# nixie-clock.net
KiCad netlist of a schematic drawn in EAGLE
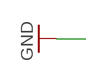
[diagram p0: schematic, sheet 1, part 1 of 2]
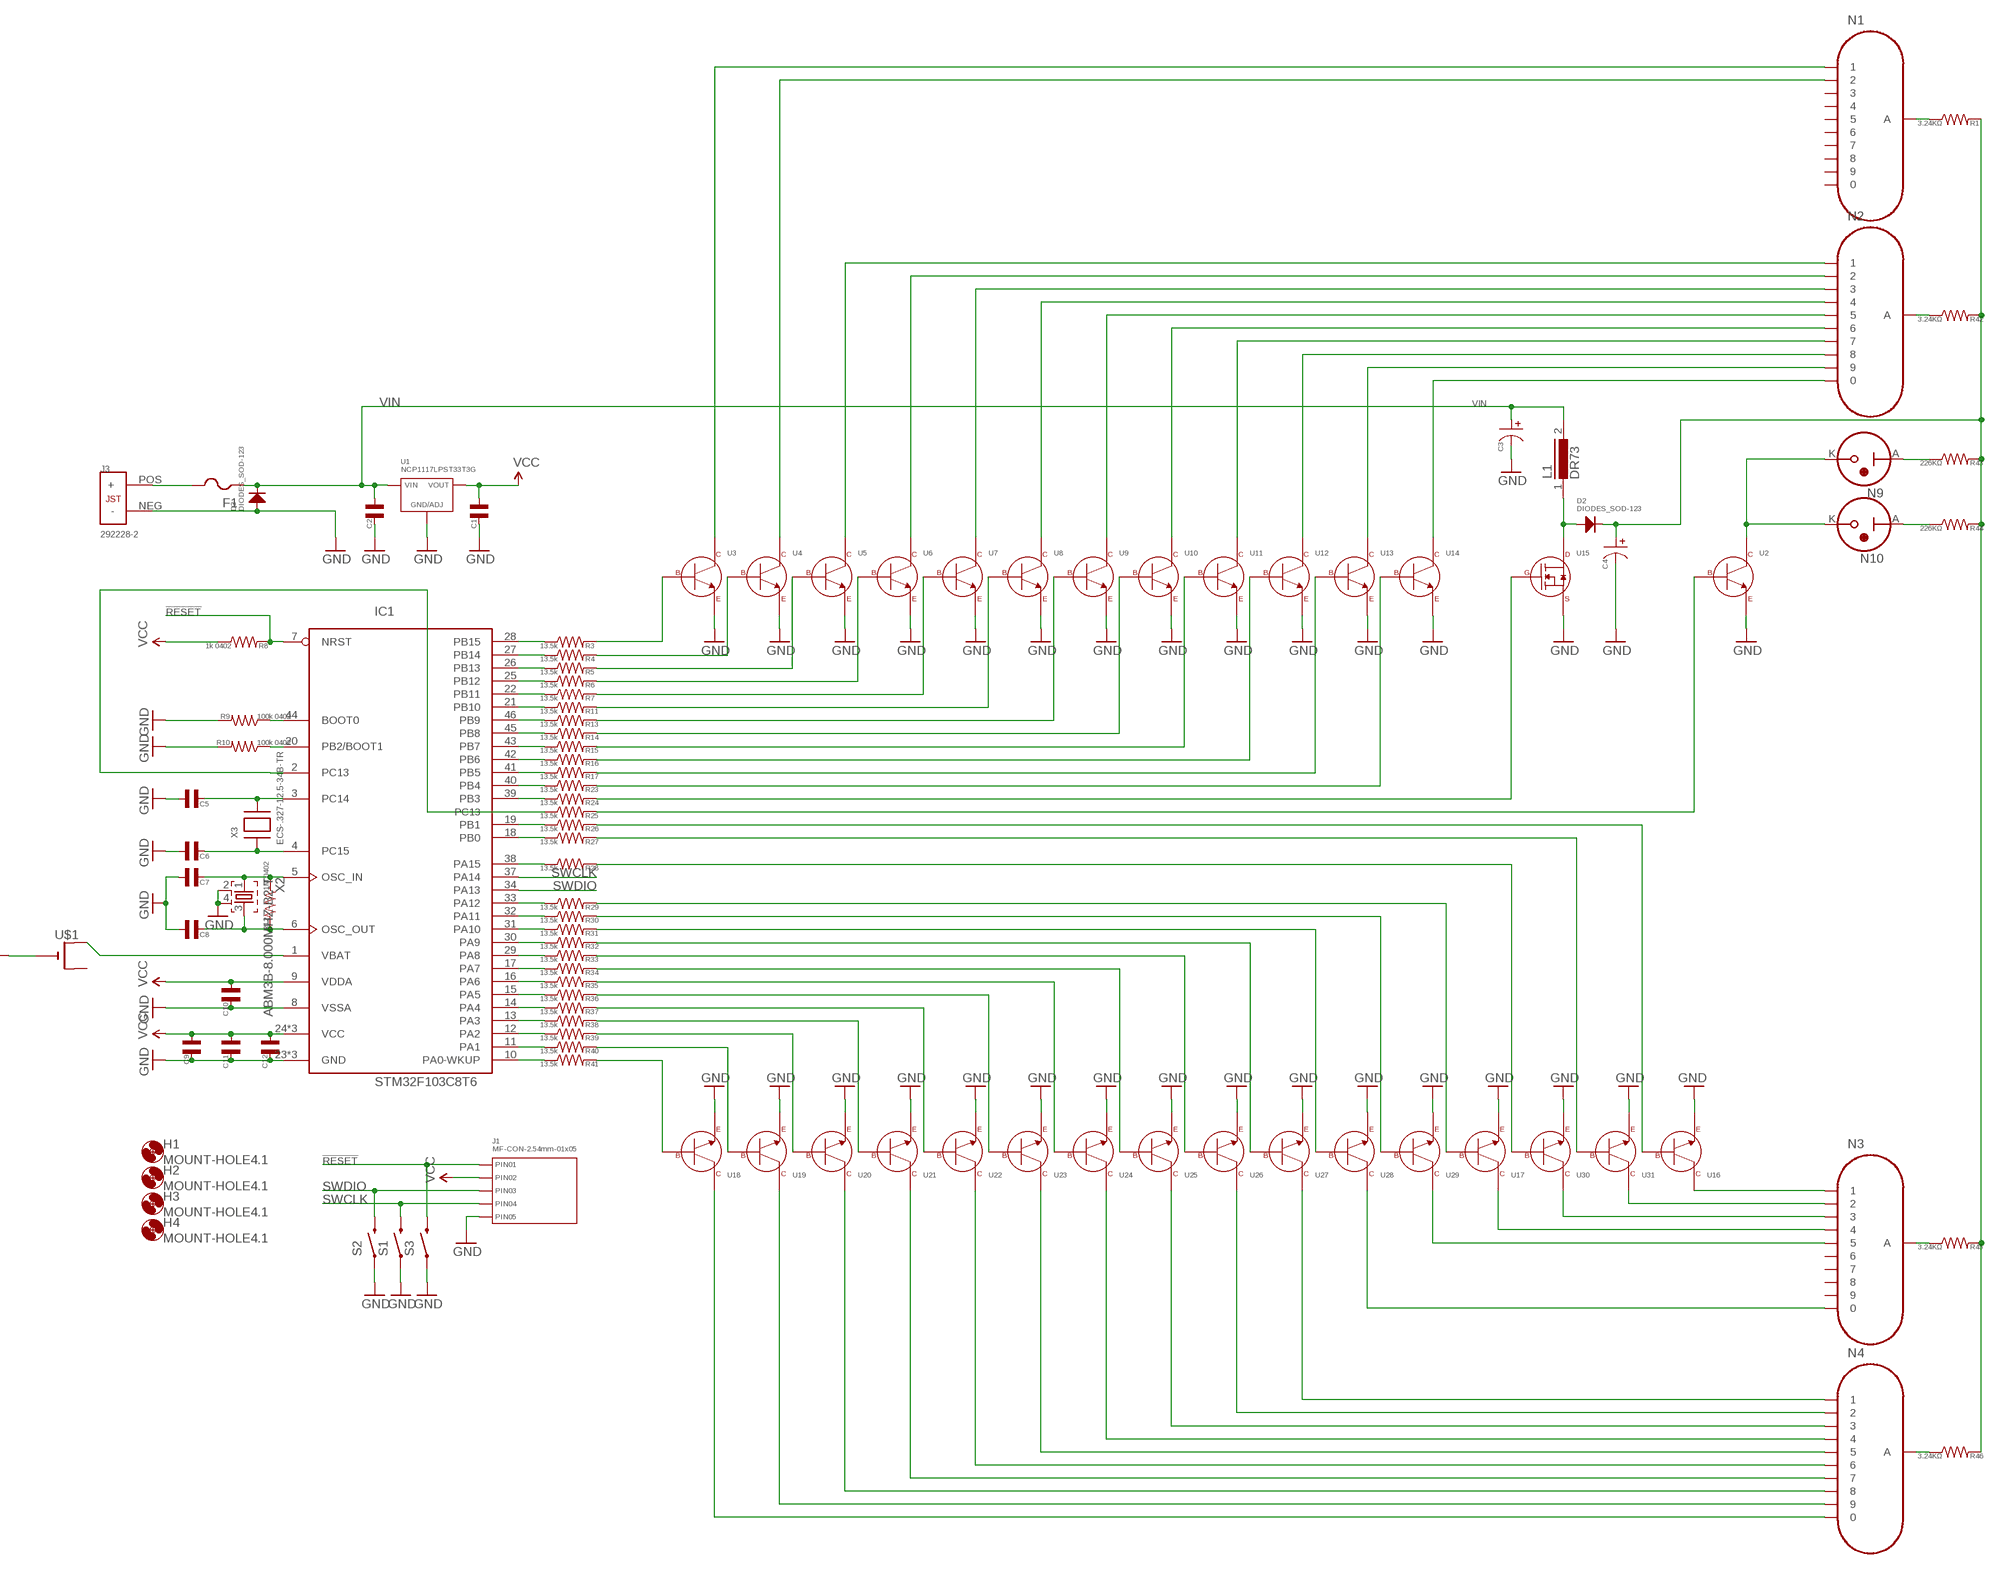
[diagram p1: schematic, sheet 1, part 2 of 2]

(export (version "E")
  (design (tool "Eeschema 10.0.6"))
  (components
    (comp (ref "C1")
      (value "CAPACITOR_NP_1206")
      (footprint "eagle-import:C1206")
      (libsource (lib "eagle-import") (part "CAPACITOR_NP_1206"))
    )
    (comp (ref "C2")
      (value "CAPACITOR_NP_1206")
      (footprint "eagle-import:C1206")
      (libsource (lib "eagle-import") (part "CAPACITOR_NP_1206"))
    )
    (comp (ref "C3")
      (value "CAPACITOR_P_6.3MM")
      (footprint "eagle-import:CP6.3MM")
      (libsource (lib "eagle-import") (part "CAPACITOR_P_6.3MM"))
    )
    (comp (ref "C4")
      (value "CAPACITOR_P_6.3MM")
      (footprint "eagle-import:CP6.3MM")
      (libsource (lib "eagle-import") (part "CAPACITOR_P_6.3MM"))
    )
    (comp (ref "C5")
      (value "CAPACITOR_NP_0402")
      (footprint "eagle-import:C0402")
      (libsource (lib "eagle-import") (part "CAPACITOR_NP_0402"))
    )
    (comp (ref "C6")
      (value "CAPACITOR_NP_0402")
      (footprint "eagle-import:C0402")
      (libsource (lib "eagle-import") (part "CAPACITOR_NP_0402"))
    )
    (comp (ref "C7")
      (value "CAPACITOR_NP_0402")
      (footprint "eagle-import:C0402")
      (libsource (lib "eagle-import") (part "CAPACITOR_NP_0402"))
    )
    (comp (ref "C8")
      (value "CAPACITOR_NP_0402")
      (footprint "eagle-import:C0402")
      (libsource (lib "eagle-import") (part "CAPACITOR_NP_0402"))
    )
    (comp (ref "C9")
      (value "CAPACITOR_NP_0402")
      (footprint "eagle-import:C0402")
      (libsource (lib "eagle-import") (part "CAPACITOR_NP_0402"))
    )
    (comp (ref "C10")
      (value "CAPACITOR_NP_0402")
      (footprint "eagle-import:C0402")
      (libsource (lib "eagle-import") (part "CAPACITOR_NP_0402"))
    )
    (comp (ref "C11")
      (value "CAPACITOR_NP_0402")
      (footprint "eagle-import:C0402")
      (libsource (lib "eagle-import") (part "CAPACITOR_NP_0402"))
    )
    (comp (ref "C12")
      (value "CAPACITOR_NP_0402")
      (footprint "eagle-import:C0402")
      (libsource (lib "eagle-import") (part "CAPACITOR_NP_0402"))
    )
    (comp (ref "D2")
      (value "DIODES_SOD-123")
      (footprint "eagle-import:SOD-123")
      (fields (field (name "HOUSEPART") "NO"))
      (libsource (lib "eagle-import") (part "DIODES_SOD-123"))
    )
    (comp (ref "D3")
      (value "DIODES_SOD-123")
      (footprint "eagle-import:SOD-123")
      (fields (field (name "HOUSEPART") "NO"))
      (libsource (lib "eagle-import") (part "DIODES_SOD-123"))
    )
    (comp (ref "F1")
      (value "PTCFUSE-1812")
      (footprint "eagle-import:1812")
      (libsource (lib "eagle-import") (part "PTCFUSE-1812"))
    )
    (comp (ref "H1")
      (value "MOUNT-HOLE4.1")
      (footprint "eagle-import:4,1")
      (libsource (lib "eagle-import") (part "MOUNT-HOLE4.1"))
    )
    (comp (ref "H2")
      (value "MOUNT-HOLE4.1")
      (footprint "eagle-import:4,1")
      (libsource (lib "eagle-import") (part "MOUNT-HOLE4.1"))
    )
    (comp (ref "H3")
      (value "MOUNT-HOLE4.1")
      (footprint "eagle-import:4,1")
      (libsource (lib "eagle-import") (part "MOUNT-HOLE4.1"))
    )
    (comp (ref "H4")
      (value "MOUNT-HOLE4.1")
      (footprint "eagle-import:4,1")
      (libsource (lib "eagle-import") (part "MOUNT-HOLE4.1"))
    )
    (comp (ref "IC1")
      (value "STM32F103C8T6")
      (footprint "eagle-import:LQFP48")
      (libsource (lib "eagle-import") (part "STM32F103CT8"))
    )
    (comp (ref "J1")
      (value "MF-CON-2.54mm-01x05")
      (footprint "eagle-import:PTH_2.54MM_01X05")
      (fields (field (name "HOUSEPART") "YES"))
      (libsource (lib "eagle-import") (part "CON_01X05_PTH_2.54MM"))
    )
    (comp (ref "J3")
      (value "292228-2")
      (footprint "eagle-import:292228-2")
      (libsource (lib "eagle-import") (part "MINICT"))
    )
    (comp (ref "L1")
      (value "DR73")
      (footprint "eagle-import:DR73")
      (libsource (lib "eagle-import") (part "DR73"))
    )
    (comp (ref "N1")
      (value "Hour1")
      (footprint "eagle-import:IN-4")
      (libsource (lib "eagle-import") (part "IN-4"))
    )
    (comp (ref "N2")
      (value "Hour2")
      (footprint "eagle-import:IN-4")
      (libsource (lib "eagle-import") (part "IN-4"))
    )
    (comp (ref "N3")
      (value "Minutes1")
      (footprint "eagle-import:IN-4")
      (libsource (lib "eagle-import") (part "IN-4"))
    )
    (comp (ref "N4")
      (value "Minutes2")
      (footprint "eagle-import:IN-4")
      (libsource (lib "eagle-import") (part "IN-4"))
    )
    (comp (ref "N9")
      (value "RainyBulb")
      (footprint "eagle-import:INS-1")
      (libsource (lib "eagle-import") (part "INS-1"))
    )
    (comp (ref "N10")
      (value "SnowyBulb")
      (footprint "eagle-import:INS-1")
      (libsource (lib "eagle-import") (part "INS-1"))
    )
    (comp (ref "R1")
      (value "3.24KΩ")
      (footprint "eagle-import:R0402")
      (libsource (lib "eagle-import") (part "RESISTOR_0402"))
    )
    (comp (ref "R3")
      (value "13.5k")
      (footprint "eagle-import:R0402")
      (libsource (lib "eagle-import") (part "RESISTOR_0402"))
    )
    (comp (ref "R4")
      (value "13.5k")
      (footprint "eagle-import:R0402")
      (libsource (lib "eagle-import") (part "RESISTOR_0402"))
    )
    (comp (ref "R5")
      (value "13.5k")
      (footprint "eagle-import:R0402")
      (libsource (lib "eagle-import") (part "RESISTOR_0402"))
    )
    (comp (ref "R6")
      (value "13.5k")
      (footprint "eagle-import:R0402")
      (libsource (lib "eagle-import") (part "RESISTOR_0402"))
    )
    (comp (ref "R7")
      (value "13.5k")
      (footprint "eagle-import:R0402")
      (libsource (lib "eagle-import") (part "RESISTOR_0402"))
    )
    (comp (ref "R8")
      (value "1k 0402")
      (footprint "eagle-import:R0402")
      (libsource (lib "eagle-import") (part "RESISTOR_0402"))
    )
    (comp (ref "R9")
      (value "100k 0402")
      (footprint "eagle-import:R0402")
      (libsource (lib "eagle-import") (part "RESISTOR_0402"))
    )
    (comp (ref "R10")
      (value "100k 0402")
      (footprint "eagle-import:R0402")
      (libsource (lib "eagle-import") (part "RESISTOR_0402"))
    )
    (comp (ref "R11")
      (value "13.5k")
      (footprint "eagle-import:R0402")
      (libsource (lib "eagle-import") (part "RESISTOR_0402"))
    )
    (comp (ref "R12")
      (value "1M 0402")
      (footprint "eagle-import:R0402")
      (libsource (lib "eagle-import") (part "RESISTOR_0402"))
    )
    (comp (ref "R13")
      (value "13.5k")
      (footprint "eagle-import:R0402")
      (libsource (lib "eagle-import") (part "RESISTOR_0402"))
    )
    (comp (ref "R14")
      (value "13.5k")
      (footprint "eagle-import:R0402")
      (libsource (lib "eagle-import") (part "RESISTOR_0402"))
    )
    (comp (ref "R15")
      (value "13.5k")
      (footprint "eagle-import:R0402")
      (libsource (lib "eagle-import") (part "RESISTOR_0402"))
    )
    (comp (ref "R16")
      (value "13.5k")
      (footprint "eagle-import:R0402")
      (libsource (lib "eagle-import") (part "RESISTOR_0402"))
    )
    (comp (ref "R17")
      (value "13.5k")
      (footprint "eagle-import:R0402")
      (libsource (lib "eagle-import") (part "RESISTOR_0402"))
    )
    (comp (ref "R23")
      (value "13.5k")
      (footprint "eagle-import:R0402")
      (libsource (lib "eagle-import") (part "RESISTOR_0402"))
    )
    (comp (ref "R24")
      (value "13.5k")
      (footprint "eagle-import:R0402")
      (libsource (lib "eagle-import") (part "RESISTOR_0402"))
    )
    (comp (ref "R25")
      (value "13.5k")
      (footprint "eagle-import:R0402")
      (libsource (lib "eagle-import") (part "RESISTOR_0402"))
    )
    (comp (ref "R26")
      (value "13.5k")
      (footprint "eagle-import:R0402")
      (libsource (lib "eagle-import") (part "RESISTOR_0402"))
    )
    (comp (ref "R27")
      (value "13.5k")
      (footprint "eagle-import:R0402")
      (libsource (lib "eagle-import") (part "RESISTOR_0402"))
    )
    (comp (ref "R28")
      (value "13.5k")
      (footprint "eagle-import:R0402")
      (libsource (lib "eagle-import") (part "RESISTOR_0402"))
    )
    (comp (ref "R29")
      (value "13.5k")
      (footprint "eagle-import:R0402")
      (libsource (lib "eagle-import") (part "RESISTOR_0402"))
    )
    (comp (ref "R30")
      (value "13.5k")
      (footprint "eagle-import:R0402")
      (libsource (lib "eagle-import") (part "RESISTOR_0402"))
    )
    (comp (ref "R31")
      (value "13.5k")
      (footprint "eagle-import:R0402")
      (libsource (lib "eagle-import") (part "RESISTOR_0402"))
    )
    (comp (ref "R32")
      (value "13.5k")
      (footprint "eagle-import:R0402")
      (libsource (lib "eagle-import") (part "RESISTOR_0402"))
    )
    (comp (ref "R33")
      (value "13.5k")
      (footprint "eagle-import:R0402")
      (libsource (lib "eagle-import") (part "RESISTOR_0402"))
    )
    (comp (ref "R34")
      (value "13.5k")
      (footprint "eagle-import:R0402")
      (libsource (lib "eagle-import") (part "RESISTOR_0402"))
    )
    (comp (ref "R35")
      (value "13.5k")
      (footprint "eagle-import:R0402")
      (libsource (lib "eagle-import") (part "RESISTOR_0402"))
    )
    (comp (ref "R36")
      (value "13.5k")
      (footprint "eagle-import:R0402")
      (libsource (lib "eagle-import") (part "RESISTOR_0402"))
    )
    (comp (ref "R37")
      (value "13.5k")
      (footprint "eagle-import:R0402")
      (libsource (lib "eagle-import") (part "RESISTOR_0402"))
    )
    (comp (ref "R38")
      (value "13.5k")
      (footprint "eagle-import:R0402")
      (libsource (lib "eagle-import") (part "RESISTOR_0402"))
    )
    (comp (ref "R39")
      (value "13.5k")
      (footprint "eagle-import:R0402")
      (libsource (lib "eagle-import") (part "RESISTOR_0402"))
    )
    (comp (ref "R40")
      (value "13.5k")
      (footprint "eagle-import:R0402")
      (libsource (lib "eagle-import") (part "RESISTOR_0402"))
    )
    (comp (ref "R41")
      (value "13.5k")
      (footprint "eagle-import:R0402")
      (libsource (lib "eagle-import") (part "RESISTOR_0402"))
    )
    (comp (ref "R42")
      (value "3.24KΩ")
      (footprint "eagle-import:R0402")
      (libsource (lib "eagle-import") (part "RESISTOR_0402"))
    )
    (comp (ref "R43")
      (value "226KΩ")
      (footprint "eagle-import:R0402")
      (libsource (lib "eagle-import") (part "RESISTOR_0402"))
    )
    (comp (ref "R44")
      (value "226KΩ")
      (footprint "eagle-import:R0402")
      (libsource (lib "eagle-import") (part "RESISTOR_0402"))
    )
    (comp (ref "R45")
      (value "3.24KΩ")
      (footprint "eagle-import:R0402")
      (libsource (lib "eagle-import") (part "RESISTOR_0402"))
    )
    (comp (ref "R46")
      (value "3.24KΩ")
      (footprint "eagle-import:R0402")
      (libsource (lib "eagle-import") (part "RESISTOR_0402"))
    )
    (comp (ref "S1")
      (value "SWITCH-MOMENTARY-2TACTILE-SWITCH-SMD-RIGHT-ANGLE")
      (footprint "eagle-import:TACTILE_SWITCH-SMD-RIGHT-ANGLE")
      (libsource (lib "eagle-import") (part "SWITCH-MOMENTARY-2TACTILE-SWITCH-SMD-RIGHT-ANGLE"))
    )
    (comp (ref "S2")
      (value "SWITCH-MOMENTARY-2TACTILE-SWITCH-SMD-RIGHT-ANGLE")
      (footprint "eagle-import:TACTILE_SWITCH-SMD-RIGHT-ANGLE")
      (libsource (lib "eagle-import") (part "SWITCH-MOMENTARY-2TACTILE-SWITCH-SMD-RIGHT-ANGLE"))
    )
    (comp (ref "S3")
      (value "SWITCH-MOMENTARY-2TACTILE-SWITCH-SMD-RIGHT-ANGLE")
      (footprint "eagle-import:TACTILE_SWITCH-SMD-RIGHT-ANGLE")
      (libsource (lib "eagle-import") (part "SWITCH-MOMENTARY-2TACTILE-SWITCH-SMD-RIGHT-ANGLE"))
    )
    (comp (ref "U$1")
      (value "CR1220SMT")
      (footprint "eagle-import:CR1220-SMD")
      (libsource (lib "eagle-import") (part "CR1220SMT"))
    )
    (comp (ref "U1")
      (value "NCP1117LPST33T3G")
      (footprint "eagle-import:SOT-223-3")
      (fields (field (name "HOUSEPART") "NO"))
      (libsource (lib "eagle-import") (part "NCP1117LPST33T3G"))
    )
    (comp (ref "U2")
      (value "NPN_BJT_SOT-23-3")
      (footprint "eagle-import:SOT-23-3")
      (fields (field (name "HOUSEPART") "NO"))
      (libsource (lib "eagle-import") (part "NPN_BJT_SOT-23-3"))
    )
    (comp (ref "U3")
      (value "NPN_BJT_SOT-23-3")
      (footprint "eagle-import:SOT-23-3")
      (fields (field (name "HOUSEPART") "NO"))
      (libsource (lib "eagle-import") (part "NPN_BJT_SOT-23-3"))
    )
    (comp (ref "U4")
      (value "NPN_BJT_SOT-23-3")
      (footprint "eagle-import:SOT-23-3")
      (fields (field (name "HOUSEPART") "NO"))
      (libsource (lib "eagle-import") (part "NPN_BJT_SOT-23-3"))
    )
    (comp (ref "U5")
      (value "NPN_BJT_SOT-23-3")
      (footprint "eagle-import:SOT-23-3")
      (fields (field (name "HOUSEPART") "NO"))
      (libsource (lib "eagle-import") (part "NPN_BJT_SOT-23-3"))
    )
    (comp (ref "U6")
      (value "NPN_BJT_SOT-23-3")
      (footprint "eagle-import:SOT-23-3")
      (fields (field (name "HOUSEPART") "NO"))
      (libsource (lib "eagle-import") (part "NPN_BJT_SOT-23-3"))
    )
    (comp (ref "U7")
      (value "NPN_BJT_SOT-23-3")
      (footprint "eagle-import:SOT-23-3")
      (fields (field (name "HOUSEPART") "NO"))
      (libsource (lib "eagle-import") (part "NPN_BJT_SOT-23-3"))
    )
    (comp (ref "U8")
      (value "NPN_BJT_SOT-23-3")
      (footprint "eagle-import:SOT-23-3")
      (fields (field (name "HOUSEPART") "NO"))
      (libsource (lib "eagle-import") (part "NPN_BJT_SOT-23-3"))
    )
    (comp (ref "U9")
      (value "NPN_BJT_SOT-23-3")
      (footprint "eagle-import:SOT-23-3")
      (fields (field (name "HOUSEPART") "NO"))
      (libsource (lib "eagle-import") (part "NPN_BJT_SOT-23-3"))
    )
    (comp (ref "U10")
      (value "NPN_BJT_SOT-23-3")
      (footprint "eagle-import:SOT-23-3")
      (fields (field (name "HOUSEPART") "NO"))
      (libsource (lib "eagle-import") (part "NPN_BJT_SOT-23-3"))
    )
    (comp (ref "U11")
      (value "NPN_BJT_SOT-23-3")
      (footprint "eagle-import:SOT-23-3")
      (fields (field (name "HOUSEPART") "NO"))
      (libsource (lib "eagle-import") (part "NPN_BJT_SOT-23-3"))
    )
    (comp (ref "U12")
      (value "NPN_BJT_SOT-23-3")
      (footprint "eagle-import:SOT-23-3")
      (fields (field (name "HOUSEPART") "NO"))
      (libsource (lib "eagle-import") (part "NPN_BJT_SOT-23-3"))
    )
    (comp (ref "U13")
      (value "NPN_BJT_SOT-23-3")
      (footprint "eagle-import:SOT-23-3")
      (fields (field (name "HOUSEPART") "NO"))
      (libsource (lib "eagle-import") (part "NPN_BJT_SOT-23-3"))
    )
    (comp (ref "U14")
      (value "NPN_BJT_SOT-23-3")
      (footprint "eagle-import:SOT-23-3")
      (fields (field (name "HOUSEPART") "NO"))
      (libsource (lib "eagle-import") (part "NPN_BJT_SOT-23-3"))
    )
    (comp (ref "U15")
      (value "N-CHANNEL_FET_TO-252-3")
      (footprint "eagle-import:TO-252-3")
      (fields (field (name "HOUSEPART") "NO"))
      (libsource (lib "eagle-import") (part "N-CHANNEL_FET_TO-252-3"))
    )
    (comp (ref "U16")
      (value "NPN_BJT_SOT-23-3")
      (footprint "eagle-import:SOT-23-3")
      (fields (field (name "HOUSEPART") "NO"))
      (libsource (lib "eagle-import") (part "NPN_BJT_SOT-23-3"))
    )
    (comp (ref "U17")
      (value "NPN_BJT_SOT-23-3")
      (footprint "eagle-import:SOT-23-3")
      (fields (field (name "HOUSEPART") "NO"))
      (libsource (lib "eagle-import") (part "NPN_BJT_SOT-23-3"))
    )
    (comp (ref "U18")
      (value "NPN_BJT_SOT-23-3")
      (footprint "eagle-import:SOT-23-3")
      (fields (field (name "HOUSEPART") "NO"))
      (libsource (lib "eagle-import") (part "NPN_BJT_SOT-23-3"))
    )
    (comp (ref "U19")
      (value "NPN_BJT_SOT-23-3")
      (footprint "eagle-import:SOT-23-3")
      (fields (field (name "HOUSEPART") "NO"))
      (libsource (lib "eagle-import") (part "NPN_BJT_SOT-23-3"))
    )
    (comp (ref "U20")
      (value "NPN_BJT_SOT-23-3")
      (footprint "eagle-import:SOT-23-3")
      (fields (field (name "HOUSEPART") "NO"))
      (libsource (lib "eagle-import") (part "NPN_BJT_SOT-23-3"))
    )
    (comp (ref "U21")
      (value "NPN_BJT_SOT-23-3")
      (footprint "eagle-import:SOT-23-3")
      (fields (field (name "HOUSEPART") "NO"))
      (libsource (lib "eagle-import") (part "NPN_BJT_SOT-23-3"))
    )
    (comp (ref "U22")
      (value "NPN_BJT_SOT-23-3")
      (footprint "eagle-import:SOT-23-3")
      (fields (field (name "HOUSEPART") "NO"))
      (libsource (lib "eagle-import") (part "NPN_BJT_SOT-23-3"))
    )
    (comp (ref "U23")
      (value "NPN_BJT_SOT-23-3")
      (footprint "eagle-import:SOT-23-3")
      (fields (field (name "HOUSEPART") "NO"))
      (libsource (lib "eagle-import") (part "NPN_BJT_SOT-23-3"))
    )
    (comp (ref "U24")
      (value "NPN_BJT_SOT-23-3")
      (footprint "eagle-import:SOT-23-3")
      (fields (field (name "HOUSEPART") "NO"))
      (libsource (lib "eagle-import") (part "NPN_BJT_SOT-23-3"))
    )
    (comp (ref "U25")
      (value "NPN_BJT_SOT-23-3")
      (footprint "eagle-import:SOT-23-3")
      (fields (field (name "HOUSEPART") "NO"))
      (libsource (lib "eagle-import") (part "NPN_BJT_SOT-23-3"))
    )
    (comp (ref "U26")
      (value "NPN_BJT_SOT-23-3")
      (footprint "eagle-import:SOT-23-3")
      (fields (field (name "HOUSEPART") "NO"))
      (libsource (lib "eagle-import") (part "NPN_BJT_SOT-23-3"))
    )
    (comp (ref "U27")
      (value "NPN_BJT_SOT-23-3")
      (footprint "eagle-import:SOT-23-3")
      (fields (field (name "HOUSEPART") "NO"))
      (libsource (lib "eagle-import") (part "NPN_BJT_SOT-23-3"))
    )
    (comp (ref "U28")
      (value "NPN_BJT_SOT-23-3")
      (footprint "eagle-import:SOT-23-3")
      (fields (field (name "HOUSEPART") "NO"))
      (libsource (lib "eagle-import") (part "NPN_BJT_SOT-23-3"))
    )
    (comp (ref "U29")
      (value "NPN_BJT_SOT-23-3")
      (footprint "eagle-import:SOT-23-3")
      (fields (field (name "HOUSEPART") "NO"))
      (libsource (lib "eagle-import") (part "NPN_BJT_SOT-23-3"))
    )
    (comp (ref "U30")
      (value "NPN_BJT_SOT-23-3")
      (footprint "eagle-import:SOT-23-3")
      (fields (field (name "HOUSEPART") "NO"))
      (libsource (lib "eagle-import") (part "NPN_BJT_SOT-23-3"))
    )
    (comp (ref "U31")
      (value "NPN_BJT_SOT-23-3")
      (footprint "eagle-import:SOT-23-3")
      (fields (field (name "HOUSEPART") "NO"))
      (libsource (lib "eagle-import") (part "NPN_BJT_SOT-23-3"))
    )
    (comp (ref "X2")
      (value "ABM3B-8.000MHZ-B2-T")
      (footprint "eagle-import:5.2X3.4-4-PAD")
      (libsource (lib "eagle-import") (part "CRYSTALS-GND-LID-CFPX-104"))
    )
    (comp (ref "X3")
      (value "ECS-.327-12.5-34B-TR")
      (footprint "eagle-import:XTAL3215")
      (libsource (lib "eagle-import") (part "XTAL-3.2X1.5"))
    )
  )
  (nets
    (net (code "1") (name "/PC13") (class "Default")
      (node (ref "IC1") (pin "2") (pinfunction "PC13_2") (pintype "bidirectional"))
      (node (ref "R25") (pin "P$1") (pinfunction "P$1_P$1") (pintype "passive"))
    )
    (net (code "2") (name "/SWCLK") (class "Default")
      (node (ref "IC1") (pin "37") (pinfunction "PA14_37") (pintype "bidirectional"))
      (node (ref "J1") (pin "P$4") (pinfunction "PIN4_P$4") (pintype "bidirectional"))
      (node (ref "S1") (pin "2") (pinfunction "2_2") (pintype "passive"))
    )
    (net (code "3") (name "/SWDIO") (class "Default")
      (node (ref "IC1") (pin "34") (pinfunction "PA13_34") (pintype "bidirectional"))
      (node (ref "J1") (pin "P$3") (pinfunction "PIN3_P$3") (pintype "bidirectional"))
      (node (ref "S2") (pin "2") (pinfunction "2_2") (pintype "passive"))
    )
    (net (code "4") (name "/VIN") (class "Default")
      (node (ref "C2") (pin "P$1") (pinfunction "P$1_P$1") (pintype "passive"))
      (node (ref "C3") (pin "P$1") (pinfunction "P$1_P$1") (pintype "passive"))
      (node (ref "D3") (pin "CATHODE") (pinfunction "CATHODE_CATHODE") (pintype "bidirectional"))
      (node (ref "F1") (pin "1") (pinfunction "1_1") (pintype "passive"))
      (node (ref "L1") (pin "2") (pinfunction "2_2") (pintype "passive"))
      (node (ref "U1") (pin "P$4") (pinfunction "VIN_P$4") (pintype "bidirectional"))
    )
    (net (code "5") (name "/~{RESET}") (class "Default")
      (node (ref "IC1") (pin "7") (pinfunction "NRST_7") (pintype "bidirectional"))
      (node (ref "J1") (pin "P$1") (pinfunction "PIN1_P$1") (pintype "bidirectional"))
      (node (ref "R8") (pin "P$2") (pinfunction "P$2_P$2") (pintype "passive"))
      (node (ref "S3") (pin "2") (pinfunction "2_2") (pintype "passive"))
    )
    (net (code "6") (name "GND") (class "Default")
      (node (ref "C1") (pin "P$2") (pinfunction "P$2_P$2") (pintype "passive"))
      (node (ref "C10") (pin "P$2") (pinfunction "P$2_P$2") (pintype "passive"))
      (node (ref "C11") (pin "P$2") (pinfunction "P$2_P$2") (pintype "passive"))
      (node (ref "C12") (pin "P$2") (pinfunction "P$2_P$2") (pintype "passive"))
      (node (ref "C2") (pin "P$2") (pinfunction "P$2_P$2") (pintype "passive"))
      (node (ref "C3") (pin "P$2") (pinfunction "P$2_P$2") (pintype "passive"))
      (node (ref "C4") (pin "P$2") (pinfunction "P$2_P$2") (pintype "passive"))
      (node (ref "C5") (pin "P$1") (pinfunction "P$1_P$1") (pintype "passive"))
      (node (ref "C6") (pin "P$1") (pinfunction "P$1_P$1") (pintype "passive"))
      (node (ref "C7") (pin "P$1") (pinfunction "P$1_P$1") (pintype "passive"))
      (node (ref "C8") (pin "P$1") (pinfunction "P$1_P$1") (pintype "passive"))
      (node (ref "C9") (pin "P$2") (pinfunction "P$2_P$2") (pintype "passive"))
      (node (ref "D3") (pin "ANODE") (pinfunction "ANODE_ANODE") (pintype "bidirectional"))
      (node (ref "IC1") (pin "23") (pinfunction "GND_23") (pintype "bidirectional"))
      (node (ref "IC1") (pin "35") (pinfunction "GND_35") (pintype "bidirectional"))
      (node (ref "IC1") (pin "47") (pinfunction "GND_47") (pintype "bidirectional"))
      (node (ref "IC1") (pin "8") (pinfunction "VSSA_8") (pintype "power_in"))
      (node (ref "J1") (pin "P$5") (pinfunction "PIN5_P$5") (pintype "bidirectional"))
      (node (ref "J3") (pin "NEG") (pinfunction "-_NEG") (pintype "bidirectional"))
      (node (ref "R10") (pin "P$2") (pinfunction "P$2_P$2") (pintype "passive"))
      (node (ref "R9") (pin "P$2") (pinfunction "P$2_P$2") (pintype "passive"))
      (node (ref "S1") (pin "1") (pinfunction "1_1") (pintype "passive"))
      (node (ref "S2") (pin "1") (pinfunction "1_1") (pintype "passive"))
      (node (ref "S3") (pin "1") (pinfunction "1_1") (pintype "passive"))
      (node (ref "U$1") (pin "-") (pinfunction "-_-") (pintype "passive"))
      (node (ref "U1") (pin "P$2") (pinfunction "GND/ADJ_P$2") (pintype "bidirectional"))
      (node (ref "U10") (pin "P$2") (pinfunction "EMITTER_P$2") (pintype "bidirectional"))
      (node (ref "U11") (pin "P$2") (pinfunction "EMITTER_P$2") (pintype "bidirectional"))
      (node (ref "U12") (pin "P$2") (pinfunction "EMITTER_P$2") (pintype "bidirectional"))
      (node (ref "U13") (pin "P$2") (pinfunction "EMITTER_P$2") (pintype "bidirectional"))
      (node (ref "U14") (pin "P$2") (pinfunction "EMITTER_P$2") (pintype "bidirectional"))
      (node (ref "U15") (pin "2") (pinfunction "SOURCE_2") (pintype "bidirectional"))
      (node (ref "U16") (pin "P$2") (pinfunction "EMITTER_P$2") (pintype "bidirectional"))
      (node (ref "U17") (pin "P$2") (pinfunction "EMITTER_P$2") (pintype "bidirectional"))
      (node (ref "U18") (pin "P$2") (pinfunction "EMITTER_P$2") (pintype "bidirectional"))
      (node (ref "U19") (pin "P$2") (pinfunction "EMITTER_P$2") (pintype "bidirectional"))
      (node (ref "U2") (pin "P$2") (pinfunction "EMITTER_P$2") (pintype "bidirectional"))
      (node (ref "U20") (pin "P$2") (pinfunction "EMITTER_P$2") (pintype "bidirectional"))
      (node (ref "U21") (pin "P$2") (pinfunction "EMITTER_P$2") (pintype "bidirectional"))
      (node (ref "U22") (pin "P$2") (pinfunction "EMITTER_P$2") (pintype "bidirectional"))
      (node (ref "U23") (pin "P$2") (pinfunction "EMITTER_P$2") (pintype "bidirectional"))
      (node (ref "U24") (pin "P$2") (pinfunction "EMITTER_P$2") (pintype "bidirectional"))
      (node (ref "U25") (pin "P$2") (pinfunction "EMITTER_P$2") (pintype "bidirectional"))
      (node (ref "U26") (pin "P$2") (pinfunction "EMITTER_P$2") (pintype "bidirectional"))
      (node (ref "U27") (pin "P$2") (pinfunction "EMITTER_P$2") (pintype "bidirectional"))
      (node (ref "U28") (pin "P$2") (pinfunction "EMITTER_P$2") (pintype "bidirectional"))
      (node (ref "U29") (pin "P$2") (pinfunction "EMITTER_P$2") (pintype "bidirectional"))
      (node (ref "U3") (pin "P$2") (pinfunction "EMITTER_P$2") (pintype "bidirectional"))
      (node (ref "U30") (pin "P$2") (pinfunction "EMITTER_P$2") (pintype "bidirectional"))
      (node (ref "U31") (pin "P$2") (pinfunction "EMITTER_P$2") (pintype "bidirectional"))
      (node (ref "U4") (pin "P$2") (pinfunction "EMITTER_P$2") (pintype "bidirectional"))
      (node (ref "U5") (pin "P$2") (pinfunction "EMITTER_P$2") (pintype "bidirectional"))
      (node (ref "U6") (pin "P$2") (pinfunction "EMITTER_P$2") (pintype "bidirectional"))
      (node (ref "U7") (pin "P$2") (pinfunction "EMITTER_P$2") (pintype "bidirectional"))
      (node (ref "U8") (pin "P$2") (pinfunction "EMITTER_P$2") (pintype "bidirectional"))
      (node (ref "U9") (pin "P$2") (pinfunction "EMITTER_P$2") (pintype "bidirectional"))
      (node (ref "X2") (pin "2") (pinfunction "2_2") (pintype "passive"))
      (node (ref "X2") (pin "4") (pinfunction "4_4") (pintype "passive"))
    )
    (net (code "7") (name "Net-(C4-PadP$1)") (class "Default")
      (node (ref "C4") (pin "P$1") (pinfunction "P$1_P$1") (pintype "passive"))
      (node (ref "D2") (pin "CATHODE") (pinfunction "CATHODE_CATHODE") (pintype "bidirectional"))
      (node (ref "R1") (pin "P$2") (pinfunction "P$2_P$2") (pintype "passive"))
      (node (ref "R42") (pin "P$2") (pinfunction "P$2_P$2") (pintype "passive"))
      (node (ref "R43") (pin "P$2") (pinfunction "P$2_P$2") (pintype "passive"))
      (node (ref "R44") (pin "P$2") (pinfunction "P$2_P$2") (pintype "passive"))
      (node (ref "R45") (pin "P$2") (pinfunction "P$2_P$2") (pintype "passive"))
      (node (ref "R46") (pin "P$2") (pinfunction "P$2_P$2") (pintype "passive"))
    )
    (net (code "8") (name "Net-(IC1-BOOT0)") (class "Default")
      (node (ref "IC1") (pin "44") (pinfunction "BOOT0_44") (pintype "input"))
      (node (ref "R9") (pin "P$1") (pinfunction "P$1_P$1") (pintype "passive"))
    )
    (net (code "9") (name "Net-(IC1-OSC_IN)") (class "Default")
      (node (ref "C7") (pin "P$2") (pinfunction "P$2_P$2") (pintype "passive"))
      (node (ref "IC1") (pin "5") (pinfunction "OSC_IN_5") (pintype "bidirectional"))
      (node (ref "R12") (pin "P$1") (pinfunction "P$1_P$1") (pintype "passive"))
      (node (ref "X2") (pin "1") (pinfunction "1_1") (pintype "passive"))
    )
    (net (code "10") (name "Net-(IC1-OSC_OUT)") (class "Default")
      (node (ref "C8") (pin "P$2") (pinfunction "P$2_P$2") (pintype "passive"))
      (node (ref "IC1") (pin "6") (pinfunction "OSC_OUT_6") (pintype "bidirectional"))
      (node (ref "R12") (pin "P$2") (pinfunction "P$2_P$2") (pintype "passive"))
      (node (ref "X2") (pin "3") (pinfunction "3_3") (pintype "passive"))
    )
    (net (code "11") (name "Net-(IC1-PA0-WKUP)") (class "Default")
      (node (ref "IC1") (pin "10") (pinfunction "PA0-WKUP_10") (pintype "bidirectional"))
      (node (ref "R41") (pin "P$1") (pinfunction "P$1_P$1") (pintype "passive"))
    )
    (net (code "12") (name "Net-(IC1-PA1)") (class "Default")
      (node (ref "IC1") (pin "11") (pinfunction "PA1_11") (pintype "bidirectional"))
      (node (ref "R40") (pin "P$1") (pinfunction "P$1_P$1") (pintype "passive"))
    )
    (net (code "13") (name "Net-(IC1-PA2)") (class "Default")
      (node (ref "IC1") (pin "12") (pinfunction "PA2_12") (pintype "bidirectional"))
      (node (ref "R39") (pin "P$1") (pinfunction "P$1_P$1") (pintype "passive"))
    )
    (net (code "14") (name "Net-(IC1-PA3)") (class "Default")
      (node (ref "IC1") (pin "13") (pinfunction "PA3_13") (pintype "bidirectional"))
      (node (ref "R38") (pin "P$1") (pinfunction "P$1_P$1") (pintype "passive"))
    )
    (net (code "15") (name "Net-(IC1-PA4)") (class "Default")
      (node (ref "IC1") (pin "14") (pinfunction "PA4_14") (pintype "bidirectional"))
      (node (ref "R37") (pin "P$1") (pinfunction "P$1_P$1") (pintype "passive"))
    )
    (net (code "16") (name "Net-(IC1-PA5)") (class "Default")
      (node (ref "IC1") (pin "15") (pinfunction "PA5_15") (pintype "bidirectional"))
      (node (ref "R36") (pin "P$1") (pinfunction "P$1_P$1") (pintype "passive"))
    )
    (net (code "17") (name "Net-(IC1-PA6)") (class "Default")
      (node (ref "IC1") (pin "16") (pinfunction "PA6_16") (pintype "bidirectional"))
      (node (ref "R35") (pin "P$1") (pinfunction "P$1_P$1") (pintype "passive"))
    )
    (net (code "18") (name "Net-(IC1-PA7)") (class "Default")
      (node (ref "IC1") (pin "17") (pinfunction "PA7_17") (pintype "bidirectional"))
      (node (ref "R34") (pin "P$1") (pinfunction "P$1_P$1") (pintype "passive"))
    )
    (net (code "19") (name "Net-(IC1-PA8)") (class "Default")
      (node (ref "IC1") (pin "29") (pinfunction "PA8_29") (pintype "bidirectional"))
      (node (ref "R33") (pin "P$1") (pinfunction "P$1_P$1") (pintype "passive"))
    )
    (net (code "20") (name "Net-(IC1-PA9)") (class "Default")
      (node (ref "IC1") (pin "30") (pinfunction "PA9_30") (pintype "bidirectional"))
      (node (ref "R32") (pin "P$1") (pinfunction "P$1_P$1") (pintype "passive"))
    )
    (net (code "21") (name "Net-(IC1-PA10)") (class "Default")
      (node (ref "IC1") (pin "31") (pinfunction "PA10_31") (pintype "bidirectional"))
      (node (ref "R31") (pin "P$1") (pinfunction "P$1_P$1") (pintype "passive"))
    )
    (net (code "22") (name "Net-(IC1-PA11)") (class "Default")
      (node (ref "IC1") (pin "32") (pinfunction "PA11_32") (pintype "bidirectional"))
      (node (ref "R30") (pin "P$1") (pinfunction "P$1_P$1") (pintype "passive"))
    )
    (net (code "23") (name "Net-(IC1-PA12)") (class "Default")
      (node (ref "IC1") (pin "33") (pinfunction "PA12_33") (pintype "bidirectional"))
      (node (ref "R29") (pin "P$1") (pinfunction "P$1_P$1") (pintype "passive"))
    )
    (net (code "24") (name "Net-(IC1-PA15)") (class "Default")
      (node (ref "IC1") (pin "38") (pinfunction "PA15_38") (pintype "bidirectional"))
      (node (ref "R28") (pin "P$1") (pinfunction "P$1_P$1") (pintype "passive"))
    )
    (net (code "25") (name "Net-(IC1-PB0)") (class "Default")
      (node (ref "IC1") (pin "18") (pinfunction "PB0_18") (pintype "bidirectional"))
      (node (ref "R27") (pin "P$1") (pinfunction "P$1_P$1") (pintype "passive"))
    )
    (net (code "26") (name "Net-(IC1-PB1)") (class "Default")
      (node (ref "IC1") (pin "19") (pinfunction "PB1_19") (pintype "bidirectional"))
      (node (ref "R26") (pin "P$1") (pinfunction "P$1_P$1") (pintype "passive"))
    )
    (net (code "27") (name "Net-(IC1-PB2{slash}BOOT1)") (class "Default")
      (node (ref "IC1") (pin "20") (pinfunction "PB2/BOOT1_20") (pintype "bidirectional"))
      (node (ref "R10") (pin "P$1") (pinfunction "P$1_P$1") (pintype "passive"))
    )
    (net (code "28") (name "Net-(IC1-PB3)") (class "Default")
      (node (ref "IC1") (pin "39") (pinfunction "PB3_39") (pintype "bidirectional"))
      (node (ref "R24") (pin "P$1") (pinfunction "P$1_P$1") (pintype "passive"))
    )
    (net (code "29") (name "Net-(IC1-PB4)") (class "Default")
      (node (ref "IC1") (pin "40") (pinfunction "PB4_40") (pintype "bidirectional"))
      (node (ref "R23") (pin "P$1") (pinfunction "P$1_P$1") (pintype "passive"))
    )
    (net (code "30") (name "Net-(IC1-PB5)") (class "Default")
      (node (ref "IC1") (pin "41") (pinfunction "PB5_41") (pintype "bidirectional"))
      (node (ref "R17") (pin "P$1") (pinfunction "P$1_P$1") (pintype "passive"))
    )
    (net (code "31") (name "Net-(IC1-PB6)") (class "Default")
      (node (ref "IC1") (pin "42") (pinfunction "PB6_42") (pintype "bidirectional"))
      (node (ref "R16") (pin "P$1") (pinfunction "P$1_P$1") (pintype "passive"))
    )
    (net (code "32") (name "Net-(IC1-PB7)") (class "Default")
      (node (ref "IC1") (pin "43") (pinfunction "PB7_43") (pintype "bidirectional"))
      (node (ref "R15") (pin "P$1") (pinfunction "P$1_P$1") (pintype "passive"))
    )
    (net (code "33") (name "Net-(IC1-PB8)") (class "Default")
      (node (ref "IC1") (pin "45") (pinfunction "PB8_45") (pintype "bidirectional"))
      (node (ref "R14") (pin "P$1") (pinfunction "P$1_P$1") (pintype "passive"))
    )
    (net (code "34") (name "Net-(IC1-PB9)") (class "Default")
      (node (ref "IC1") (pin "46") (pinfunction "PB9_46") (pintype "bidirectional"))
      (node (ref "R13") (pin "P$1") (pinfunction "P$1_P$1") (pintype "passive"))
    )
    (net (code "35") (name "Net-(IC1-PB10)") (class "Default")
      (node (ref "IC1") (pin "21") (pinfunction "PB10_21") (pintype "bidirectional"))
      (node (ref "R11") (pin "P$1") (pinfunction "P$1_P$1") (pintype "passive"))
    )
    (net (code "36") (name "Net-(IC1-PB11)") (class "Default")
      (node (ref "IC1") (pin "22") (pinfunction "PB11_22") (pintype "bidirectional"))
      (node (ref "R7") (pin "P$1") (pinfunction "P$1_P$1") (pintype "passive"))
    )
    (net (code "37") (name "Net-(IC1-PB12)") (class "Default")
      (node (ref "IC1") (pin "25") (pinfunction "PB12_25") (pintype "bidirectional"))
      (node (ref "R6") (pin "P$1") (pinfunction "P$1_P$1") (pintype "passive"))
    )
    (net (code "38") (name "Net-(IC1-PB13)") (class "Default")
      (node (ref "IC1") (pin "26") (pinfunction "PB13_26") (pintype "bidirectional"))
      (node (ref "R5") (pin "P$1") (pinfunction "P$1_P$1") (pintype "passive"))
    )
    (net (code "39") (name "Net-(IC1-PB14)") (class "Default")
      (node (ref "IC1") (pin "27") (pinfunction "PB14_27") (pintype "bidirectional"))
      (node (ref "R4") (pin "P$1") (pinfunction "P$1_P$1") (pintype "passive"))
    )
    (net (code "40") (name "Net-(IC1-PB15)") (class "Default")
      (node (ref "IC1") (pin "28") (pinfunction "PB15_28") (pintype "bidirectional"))
      (node (ref "R3") (pin "P$1") (pinfunction "P$1_P$1") (pintype "passive"))
    )
    (net (code "41") (name "Net-(IC1-PC14)") (class "Default")
      (node (ref "C5") (pin "P$2") (pinfunction "P$2_P$2") (pintype "passive"))
      (node (ref "IC1") (pin "3") (pinfunction "PC14_3") (pintype "bidirectional"))
      (node (ref "X3") (pin "P$2") (pinfunction "P$2_P$2") (pintype "bidirectional"))
    )
    (net (code "42") (name "Net-(IC1-PC15)") (class "Default")
      (node (ref "C6") (pin "P$2") (pinfunction "P$2_P$2") (pintype "passive"))
      (node (ref "IC1") (pin "4") (pinfunction "PC15_4") (pintype "bidirectional"))
      (node (ref "X3") (pin "P$1") (pinfunction "P$1_P$1") (pintype "bidirectional"))
    )
    (net (code "43") (name "Net-(IC1-VBAT)") (class "Default")
      (node (ref "IC1") (pin "1") (pinfunction "VBAT_1") (pintype "power_in"))
      (node (ref "U$1") (pin "+$1") (pinfunction "+_+$1") (pintype "passive"))
    )
    (net (code "44") (name "Net-(J3-+)") (class "Default")
      (node (ref "F1") (pin "2") (pinfunction "2_2") (pintype "passive"))
      (node (ref "J3") (pin "POS") (pinfunction "+_POS") (pintype "bidirectional"))
    )
    (net (code "45") (name "Net-(N1-1)") (class "Default")
      (node (ref "N1") (pin "14") (pinfunction "1_14") (pintype "bidirectional"))
      (node (ref "U3") (pin "P$3") (pinfunction "COLLECTOR_P$3") (pintype "bidirectional"))
    )
    (net (code "46") (name "Net-(N1-2)") (class "Default")
      (node (ref "N1") (pin "9") (pinfunction "2_9") (pintype "bidirectional"))
      (node (ref "U4") (pin "P$3") (pinfunction "COLLECTOR_P$3") (pintype "bidirectional"))
    )
    (net (code "47") (name "Net-(N1-A)") (class "Default")
      (node (ref "N1") (pin "4") (pinfunction "A_4") (pintype "bidirectional"))
      (node (ref "R1") (pin "P$1") (pinfunction "P$1_P$1") (pintype "passive"))
    )
    (net (code "48") (name "Net-(N2-0)") (class "Default")
      (node (ref "N2") (pin "8") (pinfunction "0_8") (pintype "bidirectional"))
      (node (ref "U14") (pin "P$3") (pinfunction "COLLECTOR_P$3") (pintype "bidirectional"))
    )
    (net (code "49") (name "Net-(N2-1)") (class "Default")
      (node (ref "N2") (pin "14") (pinfunction "1_14") (pintype "bidirectional"))
      (node (ref "U5") (pin "P$3") (pinfunction "COLLECTOR_P$3") (pintype "bidirectional"))
    )
    (net (code "50") (name "Net-(N2-2)") (class "Default")
      (node (ref "N2") (pin "9") (pinfunction "2_9") (pintype "bidirectional"))
      (node (ref "U6") (pin "P$3") (pinfunction "COLLECTOR_P$3") (pintype "bidirectional"))
    )
    (net (code "51") (name "Net-(N2-3)") (class "Default")
      (node (ref "N2") (pin "11") (pinfunction "3_11") (pintype "bidirectional"))
      (node (ref "U7") (pin "P$3") (pinfunction "COLLECTOR_P$3") (pintype "bidirectional"))
    )
    (net (code "52") (name "Net-(N2-4)") (class "Default")
      (node (ref "N2") (pin "1") (pinfunction "4_1") (pintype "bidirectional"))
      (node (ref "U8") (pin "P$3") (pinfunction "COLLECTOR_P$3") (pintype "bidirectional"))
    )
    (net (code "53") (name "Net-(N2-5)") (class "Default")
      (node (ref "N2") (pin "12") (pinfunction "5_12") (pintype "bidirectional"))
      (node (ref "U9") (pin "P$3") (pinfunction "COLLECTOR_P$3") (pintype "bidirectional"))
    )
    (net (code "54") (name "Net-(N2-6)") (class "Default")
      (node (ref "N2") (pin "2") (pinfunction "6_2") (pintype "bidirectional"))
      (node (ref "U10") (pin "P$3") (pinfunction "COLLECTOR_P$3") (pintype "bidirectional"))
    )
    (net (code "55") (name "Net-(N2-7)") (class "Default")
      (node (ref "N2") (pin "6") (pinfunction "7_6") (pintype "bidirectional"))
      (node (ref "U11") (pin "P$3") (pinfunction "COLLECTOR_P$3") (pintype "bidirectional"))
    )
    (net (code "56") (name "Net-(N2-8)") (class "Default")
      (node (ref "N2") (pin "3") (pinfunction "8_3") (pintype "bidirectional"))
      (node (ref "U12") (pin "P$3") (pinfunction "COLLECTOR_P$3") (pintype "bidirectional"))
    )
    (net (code "57") (name "Net-(N2-9)") (class "Default")
      (node (ref "N2") (pin "5") (pinfunction "9_5") (pintype "bidirectional"))
      (node (ref "U13") (pin "P$3") (pinfunction "COLLECTOR_P$3") (pintype "bidirectional"))
    )
    (net (code "58") (name "Net-(N2-A)") (class "Default")
      (node (ref "N2") (pin "4") (pinfunction "A_4") (pintype "bidirectional"))
      (node (ref "R42") (pin "P$1") (pinfunction "P$1_P$1") (pintype "passive"))
    )
    (net (code "59") (name "Net-(N3-0)") (class "Default")
      (node (ref "N3") (pin "8") (pinfunction "0_8") (pintype "bidirectional"))
      (node (ref "U28") (pin "P$3") (pinfunction "COLLECTOR_P$3") (pintype "bidirectional"))
    )
    (net (code "60") (name "Net-(N3-1)") (class "Default")
      (node (ref "N3") (pin "14") (pinfunction "1_14") (pintype "bidirectional"))
      (node (ref "U16") (pin "P$3") (pinfunction "COLLECTOR_P$3") (pintype "bidirectional"))
    )
    (net (code "61") (name "Net-(N3-2)") (class "Default")
      (node (ref "N3") (pin "9") (pinfunction "2_9") (pintype "bidirectional"))
      (node (ref "U31") (pin "P$3") (pinfunction "COLLECTOR_P$3") (pintype "bidirectional"))
    )
    (net (code "62") (name "Net-(N3-3)") (class "Default")
      (node (ref "N3") (pin "11") (pinfunction "3_11") (pintype "bidirectional"))
      (node (ref "U30") (pin "P$3") (pinfunction "COLLECTOR_P$3") (pintype "bidirectional"))
    )
    (net (code "63") (name "Net-(N3-4)") (class "Default")
      (node (ref "N3") (pin "1") (pinfunction "4_1") (pintype "bidirectional"))
      (node (ref "U17") (pin "P$3") (pinfunction "COLLECTOR_P$3") (pintype "bidirectional"))
    )
    (net (code "64") (name "Net-(N3-5)") (class "Default")
      (node (ref "N3") (pin "12") (pinfunction "5_12") (pintype "bidirectional"))
      (node (ref "U29") (pin "P$3") (pinfunction "COLLECTOR_P$3") (pintype "bidirectional"))
    )
    (net (code "65") (name "Net-(N3-A)") (class "Default")
      (node (ref "N3") (pin "4") (pinfunction "A_4") (pintype "bidirectional"))
      (node (ref "R45") (pin "P$1") (pinfunction "P$1_P$1") (pintype "passive"))
    )
    (net (code "66") (name "Net-(N4-0)") (class "Default")
      (node (ref "N4") (pin "8") (pinfunction "0_8") (pintype "bidirectional"))
      (node (ref "U18") (pin "P$3") (pinfunction "COLLECTOR_P$3") (pintype "bidirectional"))
    )
    (net (code "67") (name "Net-(N4-1)") (class "Default")
      (node (ref "N4") (pin "14") (pinfunction "1_14") (pintype "bidirectional"))
      (node (ref "U27") (pin "P$3") (pinfunction "COLLECTOR_P$3") (pintype "bidirectional"))
    )
    (net (code "68") (name "Net-(N4-2)") (class "Default")
      (node (ref "N4") (pin "9") (pinfunction "2_9") (pintype "bidirectional"))
      (node (ref "U26") (pin "P$3") (pinfunction "COLLECTOR_P$3") (pintype "bidirectional"))
    )
    (net (code "69") (name "Net-(N4-3)") (class "Default")
      (node (ref "N4") (pin "11") (pinfunction "3_11") (pintype "bidirectional"))
      (node (ref "U25") (pin "P$3") (pinfunction "COLLECTOR_P$3") (pintype "bidirectional"))
    )
    (net (code "70") (name "Net-(N4-4)") (class "Default")
      (node (ref "N4") (pin "1") (pinfunction "4_1") (pintype "bidirectional"))
      (node (ref "U24") (pin "P$3") (pinfunction "COLLECTOR_P$3") (pintype "bidirectional"))
    )
    (net (code "71") (name "Net-(N4-5)") (class "Default")
      (node (ref "N4") (pin "12") (pinfunction "5_12") (pintype "bidirectional"))
      (node (ref "U23") (pin "P$3") (pinfunction "COLLECTOR_P$3") (pintype "bidirectional"))
    )
    (net (code "72") (name "Net-(N4-6)") (class "Default")
      (node (ref "N4") (pin "2") (pinfunction "6_2") (pintype "bidirectional"))
      (node (ref "U22") (pin "P$3") (pinfunction "COLLECTOR_P$3") (pintype "bidirectional"))
    )
    (net (code "73") (name "Net-(N4-7)") (class "Default")
      (node (ref "N4") (pin "6") (pinfunction "7_6") (pintype "bidirectional"))
      (node (ref "U21") (pin "P$3") (pinfunction "COLLECTOR_P$3") (pintype "bidirectional"))
    )
    (net (code "74") (name "Net-(N4-8)") (class "Default")
      (node (ref "N4") (pin "3") (pinfunction "8_3") (pintype "bidirectional"))
      (node (ref "U20") (pin "P$3") (pinfunction "COLLECTOR_P$3") (pintype "bidirectional"))
    )
    (net (code "75") (name "Net-(N4-9)") (class "Default")
      (node (ref "N4") (pin "5") (pinfunction "9_5") (pintype "bidirectional"))
      (node (ref "U19") (pin "P$3") (pinfunction "COLLECTOR_P$3") (pintype "bidirectional"))
    )
    (net (code "76") (name "Net-(N4-A)") (class "Default")
      (node (ref "N4") (pin "4") (pinfunction "A_4") (pintype "bidirectional"))
      (node (ref "R46") (pin "P$1") (pinfunction "P$1_P$1") (pintype "passive"))
    )
    (net (code "77") (name "Net-(N9-PadA)") (class "Default")
      (node (ref "N9") (pin "A") (pinfunction "A_A") (pintype "bidirectional"))
      (node (ref "R43") (pin "P$1") (pinfunction "P$1_P$1") (pintype "passive"))
    )
    (net (code "78") (name "Net-(N10-PadA)") (class "Default")
      (node (ref "N10") (pin "A") (pinfunction "A_A") (pintype "bidirectional"))
      (node (ref "R44") (pin "P$1") (pinfunction "P$1_P$1") (pintype "passive"))
    )
    (net (code "79") (name "Net-(U2-BASE)") (class "Default")
      (node (ref "R25") (pin "P$2") (pinfunction "P$2_P$2") (pintype "passive"))
      (node (ref "U2") (pin "P$1") (pinfunction "BASE_P$1") (pintype "bidirectional"))
    )
    (net (code "80") (name "Net-(U2-COLLECTOR)") (class "Default")
      (node (ref "N10") (pin "K") (pinfunction "K_K") (pintype "bidirectional"))
      (node (ref "N9") (pin "K") (pinfunction "K_K") (pintype "bidirectional"))
      (node (ref "U2") (pin "P$3") (pinfunction "COLLECTOR_P$3") (pintype "bidirectional"))
    )
    (net (code "81") (name "Net-(U3-BASE)") (class "Default")
      (node (ref "R3") (pin "P$2") (pinfunction "P$2_P$2") (pintype "passive"))
      (node (ref "U3") (pin "P$1") (pinfunction "BASE_P$1") (pintype "bidirectional"))
    )
    (net (code "82") (name "Net-(U4-BASE)") (class "Default")
      (node (ref "R4") (pin "P$2") (pinfunction "P$2_P$2") (pintype "passive"))
      (node (ref "U4") (pin "P$1") (pinfunction "BASE_P$1") (pintype "bidirectional"))
    )
    (net (code "83") (name "Net-(U5-BASE)") (class "Default")
      (node (ref "R5") (pin "P$2") (pinfunction "P$2_P$2") (pintype "passive"))
      (node (ref "U5") (pin "P$1") (pinfunction "BASE_P$1") (pintype "bidirectional"))
    )
    (net (code "84") (name "Net-(U6-BASE)") (class "Default")
      (node (ref "R6") (pin "P$2") (pinfunction "P$2_P$2") (pintype "passive"))
      (node (ref "U6") (pin "P$1") (pinfunction "BASE_P$1") (pintype "bidirectional"))
    )
    (net (code "85") (name "Net-(U7-BASE)") (class "Default")
      (node (ref "R7") (pin "P$2") (pinfunction "P$2_P$2") (pintype "passive"))
      (node (ref "U7") (pin "P$1") (pinfunction "BASE_P$1") (pintype "bidirectional"))
    )
    (net (code "86") (name "Net-(U8-BASE)") (class "Default")
      (node (ref "R11") (pin "P$2") (pinfunction "P$2_P$2") (pintype "passive"))
      (node (ref "U8") (pin "P$1") (pinfunction "BASE_P$1") (pintype "bidirectional"))
    )
    (net (code "87") (name "Net-(U9-BASE)") (class "Default")
      (node (ref "R13") (pin "P$2") (pinfunction "P$2_P$2") (pintype "passive"))
      (node (ref "U9") (pin "P$1") (pinfunction "BASE_P$1") (pintype "bidirectional"))
    )
    (net (code "88") (name "Net-(U10-BASE)") (class "Default")
      (node (ref "R14") (pin "P$2") (pinfunction "P$2_P$2") (pintype "passive"))
      (node (ref "U10") (pin "P$1") (pinfunction "BASE_P$1") (pintype "bidirectional"))
    )
    (net (code "89") (name "Net-(U11-BASE)") (class "Default")
      (node (ref "R15") (pin "P$2") (pinfunction "P$2_P$2") (pintype "passive"))
      (node (ref "U11") (pin "P$1") (pinfunction "BASE_P$1") (pintype "bidirectional"))
    )
    (net (code "90") (name "Net-(U12-BASE)") (class "Default")
      (node (ref "R16") (pin "P$2") (pinfunction "P$2_P$2") (pintype "passive"))
      (node (ref "U12") (pin "P$1") (pinfunction "BASE_P$1") (pintype "bidirectional"))
    )
    (net (code "91") (name "Net-(U13-BASE)") (class "Default")
      (node (ref "R17") (pin "P$2") (pinfunction "P$2_P$2") (pintype "passive"))
      (node (ref "U13") (pin "P$1") (pinfunction "BASE_P$1") (pintype "bidirectional"))
    )
    (net (code "92") (name "Net-(U14-BASE)") (class "Default")
      (node (ref "R23") (pin "P$2") (pinfunction "P$2_P$2") (pintype "passive"))
      (node (ref "U14") (pin "P$1") (pinfunction "BASE_P$1") (pintype "bidirectional"))
    )
    (net (code "93") (name "Net-(U15-DRAIN)") (class "Default")
      (node (ref "D2") (pin "ANODE") (pinfunction "ANODE_ANODE") (pintype "bidirectional"))
      (node (ref "L1") (pin "1") (pinfunction "1_1") (pintype "passive"))
      (node (ref "U15") (pin "PAD") (pinfunction "DRAIN_PAD") (pintype "bidirectional"))
    )
    (net (code "94") (name "Net-(U15-GATE)") (class "Default")
      (node (ref "R24") (pin "P$2") (pinfunction "P$2_P$2") (pintype "passive"))
      (node (ref "U15") (pin "1") (pinfunction "GATE_1") (pintype "bidirectional"))
    )
    (net (code "95") (name "Net-(U16-BASE)") (class "Default")
      (node (ref "R26") (pin "P$2") (pinfunction "P$2_P$2") (pintype "passive"))
      (node (ref "U16") (pin "P$1") (pinfunction "BASE_P$1") (pintype "bidirectional"))
    )
    (net (code "96") (name "Net-(U17-BASE)") (class "Default")
      (node (ref "R29") (pin "P$2") (pinfunction "P$2_P$2") (pintype "passive"))
      (node (ref "U17") (pin "P$1") (pinfunction "BASE_P$1") (pintype "bidirectional"))
    )
    (net (code "97") (name "Net-(U18-BASE)") (class "Default")
      (node (ref "R41") (pin "P$2") (pinfunction "P$2_P$2") (pintype "passive"))
      (node (ref "U18") (pin "P$1") (pinfunction "BASE_P$1") (pintype "bidirectional"))
    )
    (net (code "98") (name "Net-(U19-BASE)") (class "Default")
      (node (ref "R40") (pin "P$2") (pinfunction "P$2_P$2") (pintype "passive"))
      (node (ref "U19") (pin "P$1") (pinfunction "BASE_P$1") (pintype "bidirectional"))
    )
    (net (code "99") (name "Net-(U20-BASE)") (class "Default")
      (node (ref "R39") (pin "P$2") (pinfunction "P$2_P$2") (pintype "passive"))
      (node (ref "U20") (pin "P$1") (pinfunction "BASE_P$1") (pintype "bidirectional"))
    )
    (net (code "100") (name "Net-(U21-BASE)") (class "Default")
      (node (ref "R38") (pin "P$2") (pinfunction "P$2_P$2") (pintype "passive"))
      (node (ref "U21") (pin "P$1") (pinfunction "BASE_P$1") (pintype "bidirectional"))
    )
    (net (code "101") (name "Net-(U22-BASE)") (class "Default")
      (node (ref "R37") (pin "P$2") (pinfunction "P$2_P$2") (pintype "passive"))
      (node (ref "U22") (pin "P$1") (pinfunction "BASE_P$1") (pintype "bidirectional"))
    )
    (net (code "102") (name "Net-(U23-BASE)") (class "Default")
      (node (ref "R36") (pin "P$2") (pinfunction "P$2_P$2") (pintype "passive"))
      (node (ref "U23") (pin "P$1") (pinfunction "BASE_P$1") (pintype "bidirectional"))
    )
    (net (code "103") (name "Net-(U24-BASE)") (class "Default")
      (node (ref "R35") (pin "P$2") (pinfunction "P$2_P$2") (pintype "passive"))
      (node (ref "U24") (pin "P$1") (pinfunction "BASE_P$1") (pintype "bidirectional"))
    )
    (net (code "104") (name "Net-(U25-BASE)") (class "Default")
      (node (ref "R34") (pin "P$2") (pinfunction "P$2_P$2") (pintype "passive"))
      (node (ref "U25") (pin "P$1") (pinfunction "BASE_P$1") (pintype "bidirectional"))
    )
    (net (code "105") (name "Net-(U26-BASE)") (class "Default")
      (node (ref "R33") (pin "P$2") (pinfunction "P$2_P$2") (pintype "passive"))
      (node (ref "U26") (pin "P$1") (pinfunction "BASE_P$1") (pintype "bidirectional"))
    )
    (net (code "106") (name "Net-(U27-BASE)") (class "Default")
      (node (ref "R32") (pin "P$2") (pinfunction "P$2_P$2") (pintype "passive"))
      (node (ref "U27") (pin "P$1") (pinfunction "BASE_P$1") (pintype "bidirectional"))
    )
    (net (code "107") (name "Net-(U28-BASE)") (class "Default")
      (node (ref "R31") (pin "P$2") (pinfunction "P$2_P$2") (pintype "passive"))
      (node (ref "U28") (pin "P$1") (pinfunction "BASE_P$1") (pintype "bidirectional"))
    )
    (net (code "108") (name "Net-(U29-BASE)") (class "Default")
      (node (ref "R30") (pin "P$2") (pinfunction "P$2_P$2") (pintype "passive"))
      (node (ref "U29") (pin "P$1") (pinfunction "BASE_P$1") (pintype "bidirectional"))
    )
    (net (code "109") (name "Net-(U30-BASE)") (class "Default")
      (node (ref "R28") (pin "P$2") (pinfunction "P$2_P$2") (pintype "passive"))
      (node (ref "U30") (pin "P$1") (pinfunction "BASE_P$1") (pintype "bidirectional"))
    )
    (net (code "110") (name "Net-(U31-BASE)") (class "Default")
      (node (ref "R27") (pin "P$2") (pinfunction "P$2_P$2") (pintype "passive"))
      (node (ref "U31") (pin "P$1") (pinfunction "BASE_P$1") (pintype "bidirectional"))
    )
    (net (code "111") (name "VCC") (class "Default")
      (node (ref "C1") (pin "P$1") (pinfunction "P$1_P$1") (pintype "passive"))
      (node (ref "C10") (pin "P$1") (pinfunction "P$1_P$1") (pintype "passive"))
      (node (ref "C11") (pin "P$1") (pinfunction "P$1_P$1") (pintype "passive"))
      (node (ref "C12") (pin "P$1") (pinfunction "P$1_P$1") (pintype "passive"))
      (node (ref "C9") (pin "P$1") (pinfunction "P$1_P$1") (pintype "passive"))
      (node (ref "IC1") (pin "24") (pinfunction "VCC_24") (pintype "bidirectional"))
      (node (ref "IC1") (pin "36") (pinfunction "VCC_36") (pintype "bidirectional"))
      (node (ref "IC1") (pin "48") (pinfunction "VCC_48") (pintype "bidirectional"))
      (node (ref "IC1") (pin "9") (pinfunction "VDDA_9") (pintype "power_in"))
      (node (ref "J1") (pin "P$2") (pinfunction "PIN2_P$2") (pintype "bidirectional"))
      (node (ref "R8") (pin "P$1") (pinfunction "P$1_P$1") (pintype "passive"))
      (node (ref "U1") (pin "P$1") (pinfunction "VOUT_P$1") (pintype "bidirectional"))
      (node (ref "U1") (pin "P$3") (pinfunction "VOUT_P$3") (pintype "bidirectional"))
    )
    (net (code "112") (name "unconnected-(N1-0-Pad8)") (class "Default")
      (node (ref "N1") (pin "8") (pinfunction "0_8") (pintype "bidirectional"))
    )
    (net (code "113") (name "unconnected-(N1-3-Pad11)") (class "Default")
      (node (ref "N1") (pin "11") (pinfunction "3_11") (pintype "bidirectional"))
    )
    (net (code "114") (name "unconnected-(N1-4-Pad1)") (class "Default")
      (node (ref "N1") (pin "1") (pinfunction "4_1") (pintype "bidirectional"))
    )
    (net (code "115") (name "unconnected-(N1-5-Pad12)") (class "Default")
      (node (ref "N1") (pin "12") (pinfunction "5_12") (pintype "bidirectional"))
    )
    (net (code "116") (name "unconnected-(N1-6-Pad2)") (class "Default")
      (node (ref "N1") (pin "2") (pinfunction "6_2") (pintype "bidirectional"))
    )
    (net (code "117") (name "unconnected-(N1-7-Pad6)") (class "Default")
      (node (ref "N1") (pin "6") (pinfunction "7_6") (pintype "bidirectional"))
    )
    (net (code "118") (name "unconnected-(N1-8-Pad3)") (class "Default")
      (node (ref "N1") (pin "3") (pinfunction "8_3") (pintype "bidirectional"))
    )
    (net (code "119") (name "unconnected-(N1-9-Pad5)") (class "Default")
      (node (ref "N1") (pin "5") (pinfunction "9_5") (pintype "bidirectional"))
    )
    (net (code "120") (name "unconnected-(N3-6-Pad2)") (class "Default")
      (node (ref "N3") (pin "2") (pinfunction "6_2") (pintype "bidirectional"))
    )
    (net (code "121") (name "unconnected-(N3-7-Pad6)") (class "Default")
      (node (ref "N3") (pin "6") (pinfunction "7_6") (pintype "bidirectional"))
    )
    (net (code "122") (name "unconnected-(N3-8-Pad3)") (class "Default")
      (node (ref "N3") (pin "3") (pinfunction "8_3") (pintype "bidirectional"))
    )
    (net (code "123") (name "unconnected-(N3-9-Pad5)") (class "Default")
      (node (ref "N3") (pin "5") (pinfunction "9_5") (pintype "bidirectional"))
    )
    (net (code "124") (name "unconnected-(U$1-+1-Pad+$2)") (class "Default")
      (node (ref "U$1") (pin "+$2") (pinfunction "+1_+$2") (pintype "passive"))
    )
  )
)
